# opamp.net
KiCad netlist of a schematic drawn in EAGLE
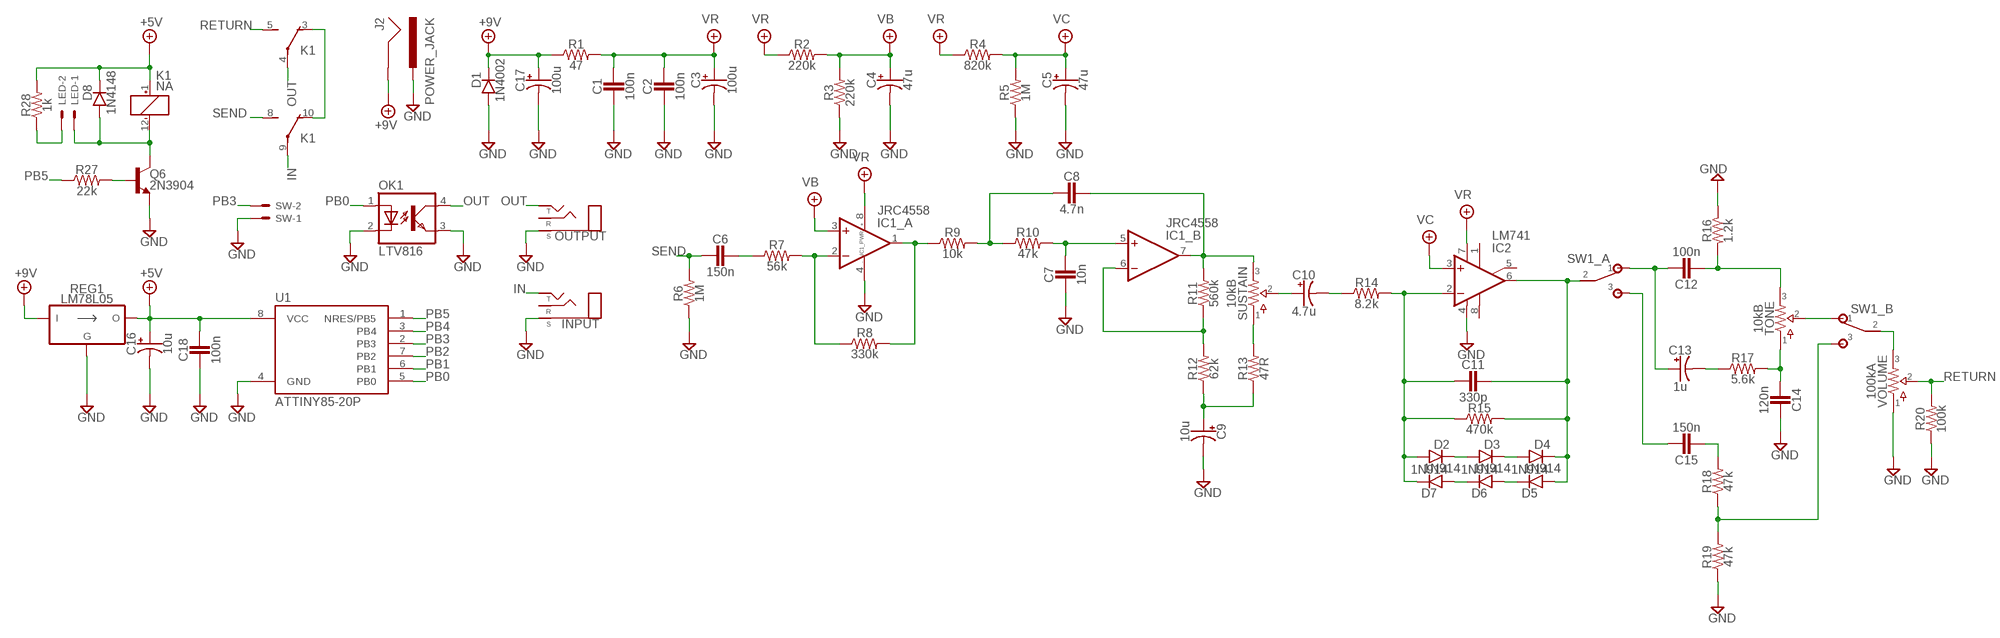
[diagram p0: schematic, sheet 1]

(export (version "E")
  (design (tool "Eeschema 10.0.6"))
  (components
    (comp (ref "C1")
      (value "100n")
      (footprint "eagle-import:050X030_025_2")
      (libsource (lib "eagle-import") (part "CER/FILM2"))
    )
    (comp (ref "C2")
      (value "100n")
      (footprint "eagle-import:050X030_025_2")
      (libsource (lib "eagle-import") (part "CER/FILM2"))
    )
    (comp (ref "C3")
      (value "100u")
      (footprint "eagle-import:050_020")
      (libsource (lib "eagle-import") (part "0500"))
    )
    (comp (ref "C4")
      (value "47u")
      (footprint "eagle-import:050_020")
      (libsource (lib "eagle-import") (part "0500"))
    )
    (comp (ref "C5")
      (value "47u")
      (footprint "eagle-import:050_020")
      (libsource (lib "eagle-import") (part "0500"))
    )
    (comp (ref "C6")
      (value "150n")
      (footprint "eagle-import:BOX_SMALL")
      (libsource (lib "eagle-import") (part "CER/FILMBOX.1"))
    )
    (comp (ref "C7")
      (value "10n")
      (footprint "eagle-import:BOX_SMALL")
      (libsource (lib "eagle-import") (part "CER/FILMBOX.1"))
    )
    (comp (ref "C8")
      (value "4.7n")
      (footprint "eagle-import:BOX_SMALL")
      (libsource (lib "eagle-import") (part "CER/FILMBOX.1"))
    )
    (comp (ref "C9")
      (value "10u")
      (footprint "eagle-import:050_020")
      (libsource (lib "eagle-import") (part "0500"))
    )
    (comp (ref "C10")
      (value "4.7u")
      (footprint "eagle-import:050_020")
      (libsource (lib "eagle-import") (part "0500"))
    )
    (comp (ref "C11")
      (value "330p")
      (footprint "eagle-import:050X030_025_2")
      (libsource (lib "eagle-import") (part "CER/FILM2"))
    )
    (comp (ref "C12")
      (value "100n")
      (footprint "eagle-import:BOX_SMALL")
      (libsource (lib "eagle-import") (part "CER/FILMBOX.1"))
    )
    (comp (ref "C13")
      (value "1u")
      (footprint "eagle-import:040_020")
      (libsource (lib "eagle-import") (part "0400"))
    )
    (comp (ref "C14")
      (value "120n")
      (footprint "eagle-import:050X030_025_2")
      (libsource (lib "eagle-import") (part "CER/FILM2"))
    )
    (comp (ref "C15")
      (value "150n")
      (footprint "eagle-import:BOX_SMALL")
      (libsource (lib "eagle-import") (part "CER/FILMBOX.1"))
    )
    (comp (ref "C16")
      (value "10u")
      (footprint "eagle-import:050_020")
      (libsource (lib "eagle-import") (part "0500"))
    )
    (comp (ref "C17")
      (value "100u")
      (footprint "eagle-import:050_020")
      (libsource (lib "eagle-import") (part "0500"))
    )
    (comp (ref "C18")
      (value "100n")
      (footprint "eagle-import:050X030_025_2")
      (libsource (lib "eagle-import") (part "CER/FILM2"))
    )
    (comp (ref "D1")
      (value "1N4002")
      (footprint "eagle-import:DO41-2")
      (libsource (lib "eagle-import") (part "DO41.2"))
    )
    (comp (ref "D2")
      (value "1N914")
      (footprint "eagle-import:DO35-2")
      (libsource (lib "eagle-import") (part "DO35.2"))
    )
    (comp (ref "D3")
      (value "1N914")
      (footprint "eagle-import:DO35-2")
      (libsource (lib "eagle-import") (part "DO35.2"))
    )
    (comp (ref "D4")
      (value "1N914")
      (footprint "eagle-import:DO35-2")
      (libsource (lib "eagle-import") (part "DO35.2"))
    )
    (comp (ref "D5")
      (value "1N914")
      (footprint "eagle-import:DO35-2")
      (libsource (lib "eagle-import") (part "DO35.2"))
    )
    (comp (ref "D6")
      (value "1N914")
      (footprint "eagle-import:DO35-2")
      (libsource (lib "eagle-import") (part "DO35.2"))
    )
    (comp (ref "D7")
      (value "1N914")
      (footprint "eagle-import:DO35-2")
      (libsource (lib "eagle-import") (part "DO35.2"))
    )
    (comp (ref "D8")
      (value "1N4148")
      (footprint "eagle-import:DO35-2")
      (libsource (lib "eagle-import") (part "DO35.2"))
    )
    (comp (ref "IC1")
      (value "JRC4558")
      (footprint "eagle-import:DIL0")
      (libsource (lib "eagle-import") (part "DUALTH"))
    )
    (comp (ref "IC2")
      (value "LM741")
      (footprint "eagle-import:DIL0")
      (libsource (lib "eagle-import") (part "SINGLETH"))
    )
    (comp (ref "INPUT")
      (value "STEREONMJ")
      (footprint "eagle-import:NMJ6HCD2")
      (libsource (lib "eagle-import") (part "STEREONMJ"))
    )
    (comp (ref "J2")
      (value "POWER_JACK")
      (footprint "eagle-import:POWER_JACK_PTH")
      (libsource (lib "eagle-import") (part "POWER_JACK"))
    )
    (comp (ref "K1") (value "NA") (footprint "eagle-import:NA") (libsource (lib "eagle-import") (part "NA")))
    (comp (ref "LED")
      (value "JST-XH-02-PIN-ROUND-PAD")
      (footprint "eagle-import:JST-XH-02-PACKAGE-ROUND-PAD")
      (libsource (lib "eagle-import") (part "JST-XH-02-PIN-ROUND-PAD"))
    )
    (comp (ref "OK1")
      (value "LTV816")
      (footprint "eagle-import:DIL04")
      (libsource (lib "eagle-import") (part "LTV816"))
    )
    (comp (ref "OUTPUT")
      (value "STEREONMJ")
      (footprint "eagle-import:NMJ6HCD2")
      (libsource (lib "eagle-import") (part "STEREONMJ"))
    )
    (comp (ref "Q6")
      (value "2N3904")
      (footprint "eagle-import:TO92-")
      (libsource (lib "eagle-import") (part "2N3904"))
    )
    (comp (ref "R1")
      (value "47")
      (footprint "eagle-import:R0207_3")
      (libsource (lib "eagle-import") (part "R_.3B"))
    )
    (comp (ref "R2")
      (value "220k")
      (footprint "eagle-import:R0207_3")
      (libsource (lib "eagle-import") (part "R_.3B"))
    )
    (comp (ref "R3")
      (value "220k")
      (footprint "eagle-import:R0207_3")
      (libsource (lib "eagle-import") (part "R_.3B"))
    )
    (comp (ref "R4")
      (value "820k")
      (footprint "eagle-import:R0207_3")
      (libsource (lib "eagle-import") (part "R_.3B"))
    )
    (comp (ref "R5")
      (value "1M")
      (footprint "eagle-import:R0207_3")
      (libsource (lib "eagle-import") (part "R_.3B"))
    )
    (comp (ref "R6")
      (value "1M")
      (footprint "eagle-import:R0207_3")
      (libsource (lib "eagle-import") (part "R_.3B"))
    )
    (comp (ref "R7")
      (value "56k")
      (footprint "eagle-import:R0207_3")
      (libsource (lib "eagle-import") (part "R_.3B"))
    )
    (comp (ref "R8")
      (value "330k")
      (footprint "eagle-import:R0207_3")
      (libsource (lib "eagle-import") (part "R_.3B"))
    )
    (comp (ref "R9")
      (value "10k")
      (footprint "eagle-import:R0207_3")
      (libsource (lib "eagle-import") (part "R_.3B"))
    )
    (comp (ref "R10")
      (value "47k")
      (footprint "eagle-import:R0207_3")
      (libsource (lib "eagle-import") (part "R_.3B"))
    )
    (comp (ref "R11")
      (value "560k")
      (footprint "eagle-import:R0207_3")
      (libsource (lib "eagle-import") (part "R_.3B"))
    )
    (comp (ref "R12")
      (value "62k")
      (footprint "eagle-import:R0207_3")
      (libsource (lib "eagle-import") (part "R_.3B"))
    )
    (comp (ref "R13")
      (value "47R")
      (footprint "eagle-import:R0207_3")
      (libsource (lib "eagle-import") (part "R_.3B"))
    )
    (comp (ref "R14")
      (value "8.2k")
      (footprint "eagle-import:R0207_3")
      (libsource (lib "eagle-import") (part "R_.3B"))
    )
    (comp (ref "R15")
      (value "470k")
      (footprint "eagle-import:R0207_3")
      (libsource (lib "eagle-import") (part "R_.3B"))
    )
    (comp (ref "R16")
      (value "1.2k")
      (footprint "eagle-import:R0207_3")
      (libsource (lib "eagle-import") (part "R_.3B"))
    )
    (comp (ref "R17")
      (value "5.6k")
      (footprint "eagle-import:R0207_3")
      (libsource (lib "eagle-import") (part "R_.3B"))
    )
    (comp (ref "R18")
      (value "47k")
      (footprint "eagle-import:R0207_3")
      (libsource (lib "eagle-import") (part "R_.3B"))
    )
    (comp (ref "R19")
      (value "47k")
      (footprint "eagle-import:R0207_3")
      (libsource (lib "eagle-import") (part "R_.3B"))
    )
    (comp (ref "R20")
      (value "100k")
      (footprint "eagle-import:R0207_3")
      (libsource (lib "eagle-import") (part "R_.3B"))
    )
    (comp (ref "R27")
      (value "22k")
      (footprint "eagle-import:R0207_3")
      (libsource (lib "eagle-import") (part "R_.3B"))
    )
    (comp (ref "R28")
      (value "1k")
      (footprint "eagle-import:R0207_3")
      (libsource (lib "eagle-import") (part "R_.3B"))
    )
    (comp (ref "REG1")
      (value "LM78L05")
      (footprint "eagle-import:TO92-")
      (libsource (lib "eagle-import") (part "LM78L05"))
    )
    (comp (ref "SUSTAIN")
      (value "10kB")
      (footprint "eagle-import:16MM")
      (libsource (lib "eagle-import") (part "POTS16MM"))
    )
    (comp (ref "SW")
      (value "JST-XH-02-PIN-ROUND-PAD")
      (footprint "eagle-import:JST-XH-02-PACKAGE-ROUND-PAD")
      (libsource (lib "eagle-import") (part "JST-XH-02-PIN-ROUND-PAD"))
    )
    (comp (ref "SW1")
      (value "DPDT")
      (footprint "eagle-import:DPDT")
      (libsource (lib "eagle-import") (part "DPDT"))
    )
    (comp (ref "TONE")
      (value "10kB")
      (footprint "eagle-import:16MM")
      (libsource (lib "eagle-import") (part "POTS16MM"))
    )
    (comp (ref "U1")
      (value "ATTINY85-20P")
      (footprint "eagle-import:PDIP08_300MIL")
      (libsource (lib "eagle-import") (part "ATTINY85P-20"))
    )
    (comp (ref "VOLUME")
      (value "100kA")
      (footprint "eagle-import:16MM")
      (libsource (lib "eagle-import") (part "POTS16MM"))
    )
  )
  (nets
    (net (code "1") (name "+5V") (class "Default")
      (node (ref "C16") (pin "+") (pinfunction "+_+") (pintype "passive"))
      (node (ref "C18") (pin "1") (pinfunction "1_1") (pintype "passive"))
      (node (ref "D8") (pin "C") (pinfunction "C_C") (pintype "passive"))
      (node (ref "K1") (pin "1") (pinfunction "+_1") (pintype "passive"))
      (node (ref "R28") (pin "2") (pinfunction "2_2") (pintype "passive"))
      (node (ref "REG1") (pin "3") (pinfunction "VO_3") (pintype "passive"))
      (node (ref "U1") (pin "8") (pinfunction "VCC_8") (pintype "power_in"))
    )
    (net (code "2") (name "+9V") (class "Default")
      (node (ref "C17") (pin "+") (pinfunction "+_+") (pintype "passive"))
      (node (ref "D1") (pin "C") (pinfunction "C_C") (pintype "passive"))
      (node (ref "J2") (pin "GND") (pinfunction "GND_GND") (pintype "bidirectional"))
      (node (ref "R1") (pin "1") (pinfunction "1_1") (pintype "passive"))
      (node (ref "REG1") (pin "1") (pinfunction "VI_1") (pintype "input"))
    )
    (net (code "3") (name "/IN") (class "Default")
      (node (ref "INPUT") (pin "T") (pinfunction "T_T") (pintype "passive"))
      (node (ref "K1") (pin "9") (pinfunction "P_9") (pintype "passive"))
    )
    (net (code "4") (name "/OUT") (class "Default")
      (node (ref "K1") (pin "4") (pinfunction "P_4") (pintype "passive"))
      (node (ref "OK1") (pin "4") (pinfunction "COL_4") (pintype "passive"))
      (node (ref "OUTPUT") (pin "T") (pinfunction "T_T") (pintype "passive"))
    )
    (net (code "5") (name "/PB0") (class "Default")
      (node (ref "OK1") (pin "1") (pinfunction "A_1") (pintype "passive"))
      (node (ref "U1") (pin "5") (pinfunction "PB0_5") (pintype "bidirectional"))
    )
    (net (code "6") (name "/PB1") (class "Default")
      (node (ref "U1") (pin "6") (pinfunction "PB1_6") (pintype "bidirectional"))
    )
    (net (code "7") (name "/PB2") (class "Default")
      (node (ref "U1") (pin "7") (pinfunction "PB2_7") (pintype "bidirectional"))
    )
    (net (code "8") (name "/PB3") (class "Default")
      (node (ref "SW") (pin "2") (pinfunction "S_2") (pintype "passive"))
      (node (ref "U1") (pin "2") (pinfunction "PB3_2") (pintype "bidirectional"))
    )
    (net (code "9") (name "/PB4") (class "Default")
      (node (ref "U1") (pin "3") (pinfunction "PB4_3") (pintype "bidirectional"))
    )
    (net (code "10") (name "/PB5") (class "Default")
      (node (ref "R27") (pin "1") (pinfunction "1_1") (pintype "passive"))
      (node (ref "U1") (pin "1") (pinfunction "NRES/PB5_1") (pintype "bidirectional"))
    )
    (net (code "11") (name "/RETURN") (class "Default")
      (node (ref "K1") (pin "5") (pinfunction "S_5") (pintype "passive"))
      (node (ref "R20") (pin "2") (pinfunction "2_2") (pintype "passive"))
      (node (ref "VOLUME") (pin "2") (pinfunction "2_2") (pintype "passive"))
    )
    (net (code "12") (name "/SEND") (class "Default")
      (node (ref "C6") (pin "1") (pinfunction "1_1") (pintype "passive"))
      (node (ref "K1") (pin "8") (pinfunction "S_8") (pintype "passive"))
      (node (ref "R6") (pin "2") (pinfunction "2_2") (pintype "passive"))
    )
    (net (code "13") (name "GND") (class "Default")
      (node (ref "C1") (pin "1") (pinfunction "1_1") (pintype "passive"))
      (node (ref "C14") (pin "1") (pinfunction "1_1") (pintype "passive"))
      (node (ref "C16") (pin "-") (pinfunction "-_-") (pintype "passive"))
      (node (ref "C17") (pin "-") (pinfunction "-_-") (pintype "passive"))
      (node (ref "C18") (pin "2") (pinfunction "2_2") (pintype "passive"))
      (node (ref "C2") (pin "1") (pinfunction "1_1") (pintype "passive"))
      (node (ref "C3") (pin "-") (pinfunction "-_-") (pintype "passive"))
      (node (ref "C4") (pin "-") (pinfunction "-_-") (pintype "passive"))
      (node (ref "C5") (pin "-") (pinfunction "-_-") (pintype "passive"))
      (node (ref "C7") (pin "1") (pinfunction "1_1") (pintype "passive"))
      (node (ref "C9") (pin "-") (pinfunction "-_-") (pintype "passive"))
      (node (ref "D1") (pin "A") (pinfunction "A_A") (pintype "passive"))
      (node (ref "IC1") (pin "4") (pinfunction "V-_4") (pintype "power_in"))
      (node (ref "IC2") (pin "4") (pinfunction "V-_4") (pintype "power_in"))
      (node (ref "INPUT") (pin "S") (pinfunction "S_S") (pintype "passive"))
      (node (ref "J2") (pin "PWR") (pinfunction "PWR_PWR") (pintype "bidirectional"))
      (node (ref "OK1") (pin "2") (pinfunction "C_2") (pintype "passive"))
      (node (ref "OK1") (pin "3") (pinfunction "EMIT_3") (pintype "passive"))
      (node (ref "OUTPUT") (pin "S") (pinfunction "S_S") (pintype "passive"))
      (node (ref "Q6") (pin "3") (pinfunction "E_3") (pintype "passive"))
      (node (ref "R16") (pin "1") (pinfunction "1_1") (pintype "passive"))
      (node (ref "R19") (pin "1") (pinfunction "1_1") (pintype "passive"))
      (node (ref "R20") (pin "1") (pinfunction "1_1") (pintype "passive"))
      (node (ref "R3") (pin "1") (pinfunction "1_1") (pintype "passive"))
      (node (ref "R5") (pin "1") (pinfunction "1_1") (pintype "passive"))
      (node (ref "R6") (pin "1") (pinfunction "1_1") (pintype "passive"))
      (node (ref "REG1") (pin "2") (pinfunction "GND_2") (pintype "passive"))
      (node (ref "SW") (pin "1") (pinfunction "S_1") (pintype "passive"))
      (node (ref "U1") (pin "4") (pinfunction "GND_4") (pintype "power_in"))
      (node (ref "VOLUME") (pin "1") (pinfunction "1_1") (pintype "passive"))
    )
    (net (code "14") (name "Net-(C6-Pad2)") (class "Default")
      (node (ref "C6") (pin "2") (pinfunction "2_2") (pintype "passive"))
      (node (ref "R7") (pin "1") (pinfunction "1_1") (pintype "passive"))
    )
    (net (code "15") (name "Net-(C8-Pad2)") (class "Default")
      (node (ref "C8") (pin "2") (pinfunction "2_2") (pintype "passive"))
      (node (ref "R10") (pin "1") (pinfunction "1_1") (pintype "passive"))
      (node (ref "R9") (pin "2") (pinfunction "2_2") (pintype "passive"))
    )
    (net (code "16") (name "Net-(C9-Pad+)") (class "Default")
      (node (ref "C9") (pin "+") (pinfunction "+_+") (pintype "passive"))
      (node (ref "R12") (pin "1") (pinfunction "1_1") (pintype "passive"))
      (node (ref "R13") (pin "1") (pinfunction "1_1") (pintype "passive"))
    )
    (net (code "17") (name "Net-(C10-Pad+)") (class "Default")
      (node (ref "C10") (pin "+") (pinfunction "+_+") (pintype "passive"))
      (node (ref "SUSTAIN") (pin "2") (pinfunction "2_2") (pintype "passive"))
    )
    (net (code "18") (name "Net-(C10-Pad-)") (class "Default")
      (node (ref "C10") (pin "-") (pinfunction "-_-") (pintype "passive"))
      (node (ref "R14") (pin "1") (pinfunction "1_1") (pintype "passive"))
    )
    (net (code "19") (name "Net-(C12-Pad2)") (class "Default")
      (node (ref "C12") (pin "2") (pinfunction "2_2") (pintype "passive"))
      (node (ref "R16") (pin "2") (pinfunction "2_2") (pintype "passive"))
      (node (ref "TONE") (pin "3") (pinfunction "3_3") (pintype "passive"))
    )
    (net (code "20") (name "Net-(C13-Pad-)") (class "Default")
      (node (ref "C13") (pin "-") (pinfunction "-_-") (pintype "passive"))
      (node (ref "R17") (pin "1") (pinfunction "1_1") (pintype "passive"))
    )
    (net (code "21") (name "Net-(C14-Pad2)") (class "Default")
      (node (ref "C14") (pin "2") (pinfunction "2_2") (pintype "passive"))
      (node (ref "R17") (pin "2") (pinfunction "2_2") (pintype "passive"))
      (node (ref "TONE") (pin "1") (pinfunction "1_1") (pintype "passive"))
    )
    (net (code "22") (name "Net-(C15-Pad2)") (class "Default")
      (node (ref "C15") (pin "2") (pinfunction "2_2") (pintype "passive"))
      (node (ref "R18") (pin "2") (pinfunction "2_2") (pintype "passive"))
    )
    (net (code "23") (name "Net-(D2-PadC)") (class "Default")
      (node (ref "D2") (pin "C") (pinfunction "C_C") (pintype "passive"))
      (node (ref "D3") (pin "A") (pinfunction "A_A") (pintype "passive"))
    )
    (net (code "24") (name "Net-(D3-PadC)") (class "Default")
      (node (ref "D3") (pin "C") (pinfunction "C_C") (pintype "passive"))
      (node (ref "D4") (pin "A") (pinfunction "A_A") (pintype "passive"))
    )
    (net (code "25") (name "Net-(D5-PadC)") (class "Default")
      (node (ref "D5") (pin "C") (pinfunction "C_C") (pintype "passive"))
      (node (ref "D6") (pin "A") (pinfunction "A_A") (pintype "passive"))
    )
    (net (code "26") (name "Net-(D6-PadC)") (class "Default")
      (node (ref "D6") (pin "C") (pinfunction "C_C") (pintype "passive"))
      (node (ref "D7") (pin "A") (pinfunction "A_A") (pintype "passive"))
    )
    (net (code "27") (name "Net-(IC1A--IN)") (class "Default")
      (node (ref "IC1") (pin "2") (pinfunction "-IN_2") (pintype "input"))
      (node (ref "R7") (pin "2") (pinfunction "2_2") (pintype "passive"))
      (node (ref "R8") (pin "1") (pinfunction "1_1") (pintype "passive"))
    )
    (net (code "28") (name "Net-(IC1A-OUT)") (class "Default")
      (node (ref "IC1") (pin "1") (pinfunction "OUT_1") (pintype "output"))
      (node (ref "R8") (pin "2") (pinfunction "2_2") (pintype "passive"))
      (node (ref "R9") (pin "1") (pinfunction "1_1") (pintype "passive"))
    )
    (net (code "29") (name "Net-(IC1B-+IN)") (class "Default")
      (node (ref "C7") (pin "2") (pinfunction "2_2") (pintype "passive"))
      (node (ref "IC1") (pin "5") (pinfunction "+IN_5") (pintype "input"))
      (node (ref "R10") (pin "2") (pinfunction "2_2") (pintype "passive"))
    )
    (net (code "30") (name "Net-(IC1B--IN)") (class "Default")
      (node (ref "IC1") (pin "6") (pinfunction "-IN_6") (pintype "input"))
      (node (ref "R11") (pin "1") (pinfunction "1_1") (pintype "passive"))
      (node (ref "R12") (pin "2") (pinfunction "2_2") (pintype "passive"))
    )
    (net (code "31") (name "Net-(IC1B-OUT)") (class "Default")
      (node (ref "C8") (pin "1") (pinfunction "1_1") (pintype "passive"))
      (node (ref "IC1") (pin "7") (pinfunction "OUT_7") (pintype "output"))
      (node (ref "R11") (pin "2") (pinfunction "2_2") (pintype "passive"))
      (node (ref "SUSTAIN") (pin "3") (pinfunction "3_3") (pintype "passive"))
    )
    (net (code "32") (name "Net-(IC2--IN)") (class "Default")
      (node (ref "C11") (pin "2") (pinfunction "2_2") (pintype "passive"))
      (node (ref "D2") (pin "A") (pinfunction "A_A") (pintype "passive"))
      (node (ref "D7") (pin "C") (pinfunction "C_C") (pintype "passive"))
      (node (ref "IC2") (pin "2") (pinfunction "-IN_2") (pintype "input"))
      (node (ref "R14") (pin "2") (pinfunction "2_2") (pintype "passive"))
      (node (ref "R15") (pin "1") (pinfunction "1_1") (pintype "passive"))
    )
    (net (code "33") (name "Net-(IC2-OUT)") (class "Default")
      (node (ref "C11") (pin "1") (pinfunction "1_1") (pintype "passive"))
      (node (ref "D4") (pin "C") (pinfunction "C_C") (pintype "passive"))
      (node (ref "D5") (pin "A") (pinfunction "A_A") (pintype "passive"))
      (node (ref "IC2") (pin "6") (pinfunction "OUT_6") (pintype "output"))
      (node (ref "R15") (pin "2") (pinfunction "2_2") (pintype "passive"))
      (node (ref "SW1") (pin "A2") (pinfunction "2_A2") (pintype "passive"))
    )
    (net (code "34") (name "Net-(K1A--)") (class "Default")
      (node (ref "D8") (pin "A") (pinfunction "A_A") (pintype "passive"))
      (node (ref "K1") (pin "12") (pinfunction "-_12") (pintype "passive"))
      (node (ref "LED") (pin "1") (pinfunction "S_1") (pintype "passive"))
      (node (ref "Q6") (pin "1") (pinfunction "C_1") (pintype "passive"))
    )
    (net (code "35") (name "Net-(K1B-O)") (class "Default")
      (node (ref "K1") (pin "10") (pinfunction "O_10") (pintype "passive"))
      (node (ref "K1") (pin "3") (pinfunction "O_3") (pintype "passive"))
    )
    (net (code "36") (name "Net-(LEDB-S)") (class "Default")
      (node (ref "LED") (pin "2") (pinfunction "S_2") (pintype "passive"))
      (node (ref "R28") (pin "1") (pinfunction "1_1") (pintype "passive"))
    )
    (net (code "37") (name "Net-(Q6-B)") (class "Default")
      (node (ref "Q6") (pin "2") (pinfunction "B_2") (pintype "passive"))
      (node (ref "R27") (pin "2") (pinfunction "2_2") (pintype "passive"))
    )
    (net (code "38") (name "Net-(R13-Pad2)") (class "Default")
      (node (ref "R13") (pin "2") (pinfunction "2_2") (pintype "passive"))
      (node (ref "SUSTAIN") (pin "1") (pinfunction "1_1") (pintype "passive"))
    )
    (net (code "39") (name "Net-(SW1A-1)") (class "Default")
      (node (ref "C12") (pin "1") (pinfunction "1_1") (pintype "passive"))
      (node (ref "C13") (pin "+") (pinfunction "+_+") (pintype "passive"))
      (node (ref "SW1") (pin "A1") (pinfunction "1_A1") (pintype "passive"))
    )
    (net (code "40") (name "Net-(SW1A-3)") (class "Default")
      (node (ref "C15") (pin "1") (pinfunction "1_1") (pintype "passive"))
      (node (ref "SW1") (pin "A3") (pinfunction "3_A3") (pintype "passive"))
    )
    (net (code "41") (name "Net-(SW1B-1)") (class "Default")
      (node (ref "SW1") (pin "B1") (pinfunction "1_B1") (pintype "passive"))
      (node (ref "TONE") (pin "2") (pinfunction "2_2") (pintype "passive"))
    )
    (net (code "42") (name "Net-(SW1B-2)") (class "Default")
      (node (ref "SW1") (pin "B2") (pinfunction "2_B2") (pintype "passive"))
      (node (ref "VOLUME") (pin "3") (pinfunction "3_3") (pintype "passive"))
    )
    (net (code "43") (name "Net-(SW1B-3)") (class "Default")
      (node (ref "R18") (pin "1") (pinfunction "1_1") (pintype "passive"))
      (node (ref "R19") (pin "2") (pinfunction "2_2") (pintype "passive"))
      (node (ref "SW1") (pin "B3") (pinfunction "3_B3") (pintype "passive"))
    )
    (net (code "44") (name "VB") (class "Default")
      (node (ref "C4") (pin "+") (pinfunction "+_+") (pintype "passive"))
      (node (ref "IC1") (pin "3") (pinfunction "+IN_3") (pintype "input"))
      (node (ref "R2") (pin "2") (pinfunction "2_2") (pintype "passive"))
      (node (ref "R3") (pin "2") (pinfunction "2_2") (pintype "passive"))
    )
    (net (code "45") (name "VC") (class "Default")
      (node (ref "C5") (pin "+") (pinfunction "+_+") (pintype "passive"))
      (node (ref "IC2") (pin "3") (pinfunction "+IN_3") (pintype "input"))
      (node (ref "R4") (pin "2") (pinfunction "2_2") (pintype "passive"))
      (node (ref "R5") (pin "2") (pinfunction "2_2") (pintype "passive"))
    )
    (net (code "46") (name "VR") (class "Default")
      (node (ref "C1") (pin "2") (pinfunction "2_2") (pintype "passive"))
      (node (ref "C2") (pin "2") (pinfunction "2_2") (pintype "passive"))
      (node (ref "C3") (pin "+") (pinfunction "+_+") (pintype "passive"))
      (node (ref "IC1") (pin "8") (pinfunction "V+_8") (pintype "power_in"))
      (node (ref "IC2") (pin "7") (pinfunction "V+_7") (pintype "power_in"))
      (node (ref "R1") (pin "2") (pinfunction "2_2") (pintype "passive"))
      (node (ref "R2") (pin "1") (pinfunction "1_1") (pintype "passive"))
      (node (ref "R4") (pin "1") (pinfunction "1_1") (pintype "passive"))
    )
    (net (code "47") (name "unconnected-(IC2-ON1-Pad1)") (class "Default")
      (node (ref "IC2") (pin "1") (pinfunction "ON1_1") (pintype "passive"))
    )
    (net (code "48") (name "unconnected-(IC2-ON2-Pad5)") (class "Default")
      (node (ref "IC2") (pin "5") (pinfunction "ON2_5") (pintype "passive"))
    )
    (net (code "49") (name "unconnected-(IC2-OPT-Pad8)") (class "Default")
      (node (ref "IC2") (pin "8") (pinfunction "OPT_8") (pintype "passive"))
    )
    (net (code "50") (name "unconnected-(INPUT-PadR)") (class "Default")
      (node (ref "INPUT") (pin "R") (pinfunction "R_R") (pintype "passive"))
    )
    (net (code "51") (name "unconnected-(OUTPUT-PadR)") (class "Default")
      (node (ref "OUTPUT") (pin "R") (pinfunction "R_R") (pintype "passive"))
    )
  )
)
